# AS3364_DG412_bus_mixer_v1_2.net
KiCad netlist of a schematic drawn in EAGLE
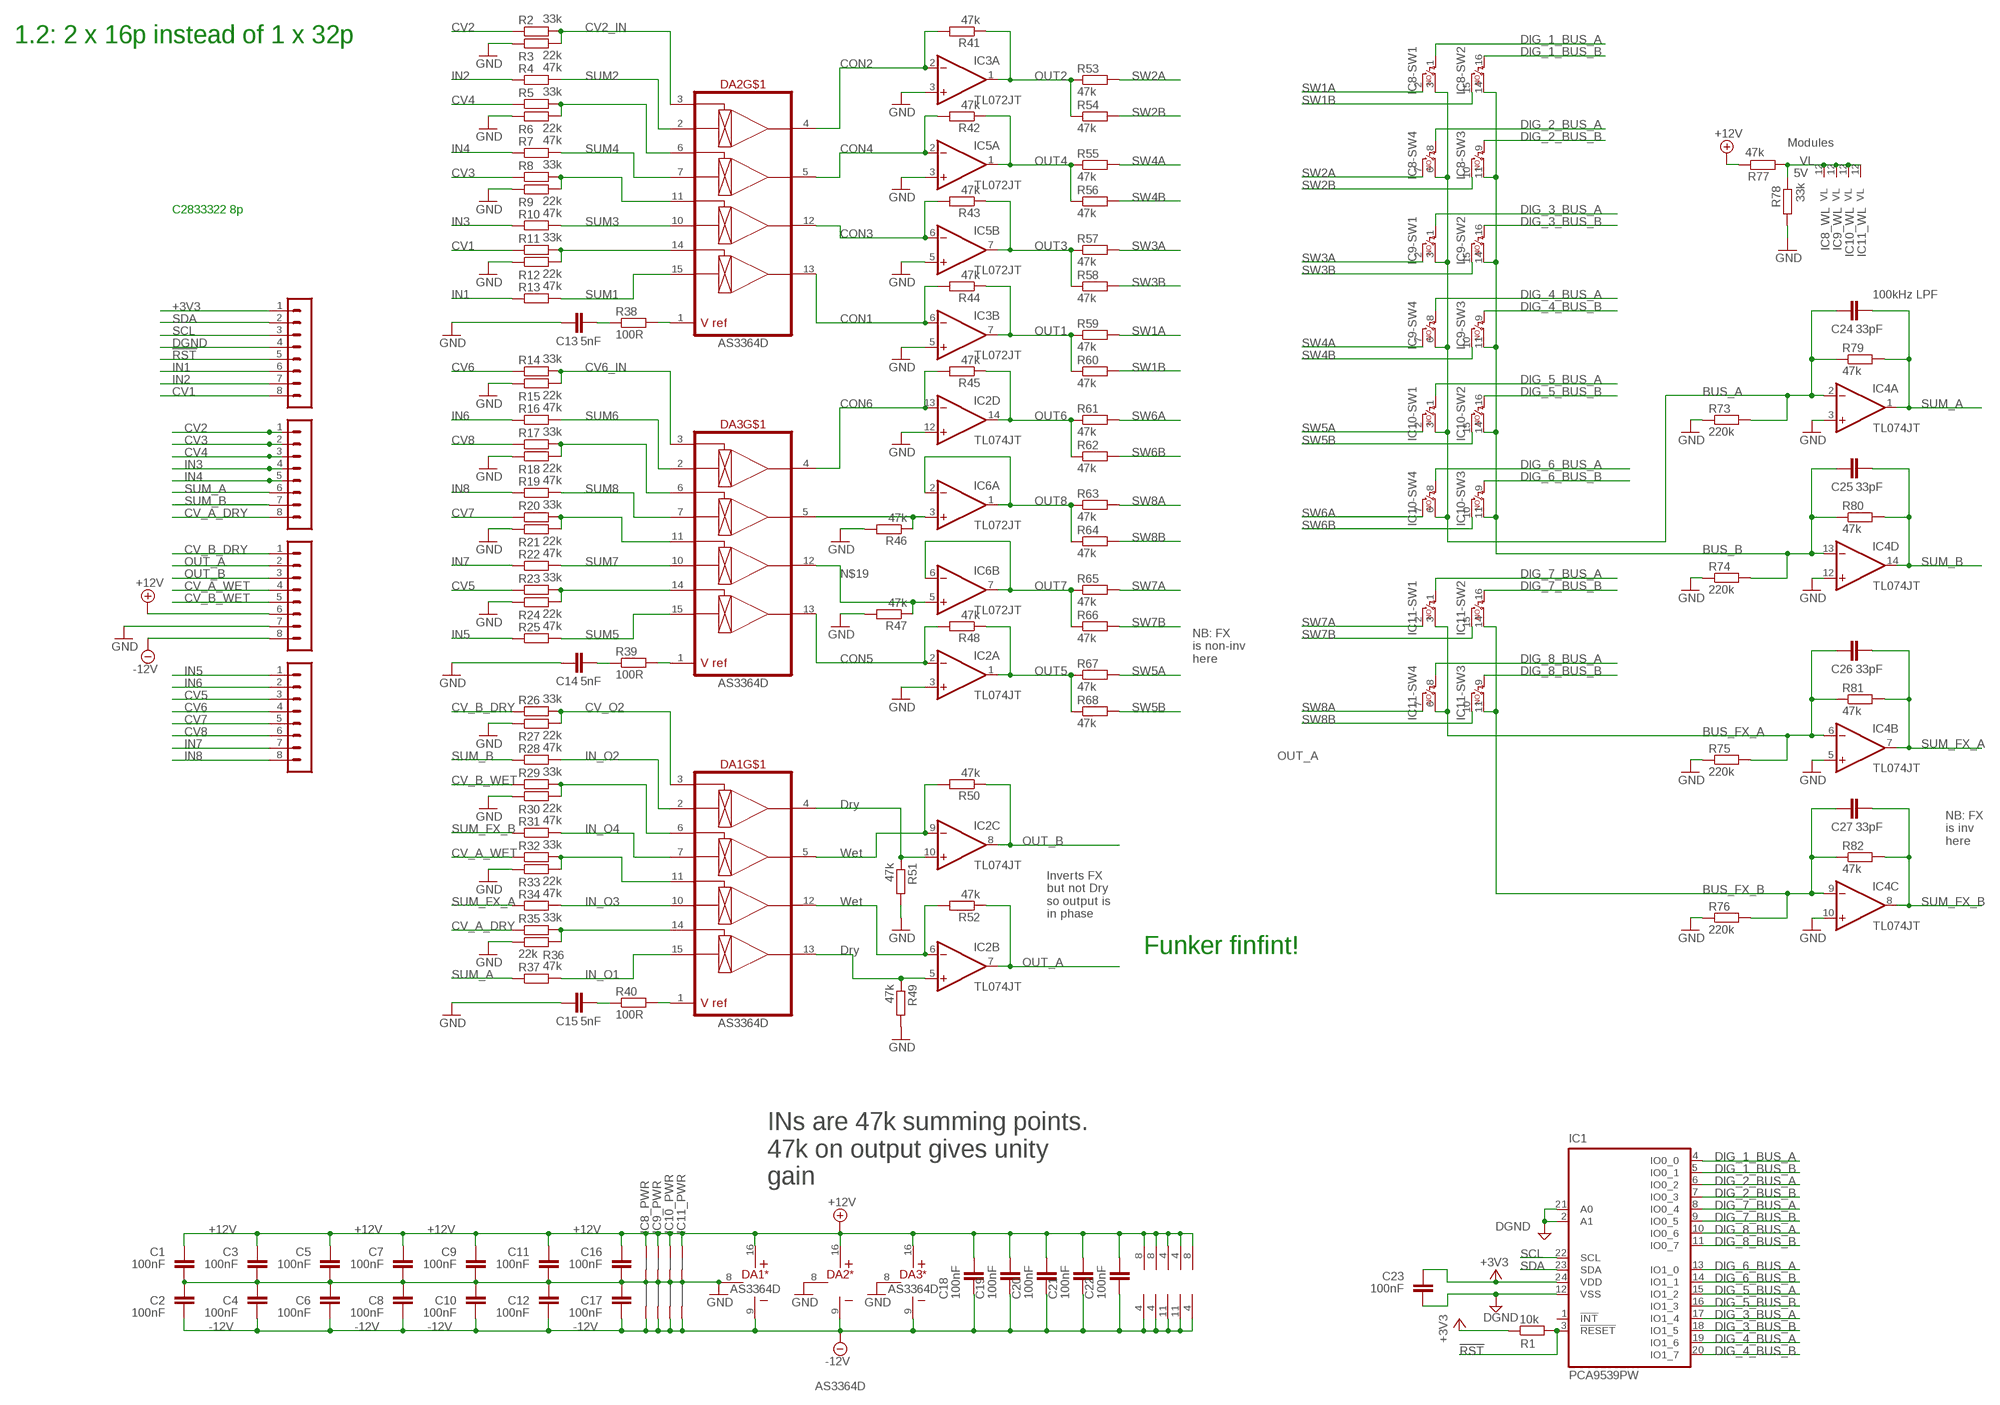
[diagram p0: schematic, sheet 1]

(export (version "E")
  (design (tool "Eeschema 10.0.6"))
  (components
    (comp (ref "C1")
      (value "100nF")
      (footprint "eagle-import:C0402")
      (libsource (lib "eagle-import") (part "C-EUC0402"))
    )
    (comp (ref "C2")
      (value "100nF")
      (footprint "eagle-import:C0402")
      (libsource (lib "eagle-import") (part "C-EUC0402"))
    )
    (comp (ref "C3")
      (value "100nF")
      (footprint "eagle-import:C0402")
      (libsource (lib "eagle-import") (part "C-EUC0402"))
    )
    (comp (ref "C4")
      (value "100nF")
      (footprint "eagle-import:C0402")
      (libsource (lib "eagle-import") (part "C-EUC0402"))
    )
    (comp (ref "C5")
      (value "100nF")
      (footprint "eagle-import:C0402")
      (libsource (lib "eagle-import") (part "C-EUC0402"))
    )
    (comp (ref "C6")
      (value "100nF")
      (footprint "eagle-import:C0402")
      (libsource (lib "eagle-import") (part "C-EUC0402"))
    )
    (comp (ref "C7")
      (value "100nF")
      (footprint "eagle-import:C0402")
      (libsource (lib "eagle-import") (part "C-EUC0402"))
    )
    (comp (ref "C8")
      (value "100nF")
      (footprint "eagle-import:C0402")
      (libsource (lib "eagle-import") (part "C-EUC0402"))
    )
    (comp (ref "C9")
      (value "100nF")
      (footprint "eagle-import:C0402")
      (libsource (lib "eagle-import") (part "C-EUC0402"))
    )
    (comp (ref "C10")
      (value "100nF")
      (footprint "eagle-import:C0402")
      (libsource (lib "eagle-import") (part "C-EUC0402"))
    )
    (comp (ref "C11")
      (value "100nF")
      (footprint "eagle-import:C0402")
      (libsource (lib "eagle-import") (part "C-EUC0402"))
    )
    (comp (ref "C12")
      (value "100nF")
      (footprint "eagle-import:C0402")
      (libsource (lib "eagle-import") (part "C-EUC0402"))
    )
    (comp (ref "C13")
      (value "5nF")
      (footprint "eagle-import:C0402-J")
      (libsource (lib "eagle-import") (part "C-EU-J"))
    )
    (comp (ref "C14")
      (value "5nF")
      (footprint "eagle-import:C0402-J")
      (libsource (lib "eagle-import") (part "C-EU-J"))
    )
    (comp (ref "C15")
      (value "5nF")
      (footprint "eagle-import:C0402-J")
      (libsource (lib "eagle-import") (part "C-EU-J"))
    )
    (comp (ref "C16")
      (value "100nF")
      (footprint "eagle-import:C0402")
      (libsource (lib "eagle-import") (part "C-EUC0402"))
    )
    (comp (ref "C17")
      (value "100nF")
      (footprint "eagle-import:C0402")
      (libsource (lib "eagle-import") (part "C-EUC0402"))
    )
    (comp (ref "C18")
      (value "100nF")
      (footprint "eagle-import:C0402")
      (libsource (lib "eagle-import") (part "C-EUC0402"))
    )
    (comp (ref "C19")
      (value "100nF")
      (footprint "eagle-import:C0402")
      (libsource (lib "eagle-import") (part "C-EUC0402"))
    )
    (comp (ref "C20")
      (value "100nF")
      (footprint "eagle-import:C0402")
      (libsource (lib "eagle-import") (part "C-EUC0402"))
    )
    (comp (ref "C21")
      (value "100nF")
      (footprint "eagle-import:C0402")
      (libsource (lib "eagle-import") (part "C-EUC0402"))
    )
    (comp (ref "C22")
      (value "100nF")
      (footprint "eagle-import:C0402")
      (libsource (lib "eagle-import") (part "C-EUC0402"))
    )
    (comp (ref "C23")
      (value "100nF")
      (footprint "eagle-import:C0402")
      (libsource (lib "eagle-import") (part "C-EUC0402"))
    )
    (comp (ref "C24")
      (value "33pF")
      (footprint "eagle-import:C0402-J")
      (libsource (lib "eagle-import") (part "C-EU-J"))
    )
    (comp (ref "C25")
      (value "33pF")
      (footprint "eagle-import:C0402-J")
      (libsource (lib "eagle-import") (part "C-EU-J"))
    )
    (comp (ref "C26")
      (value "33pF")
      (footprint "eagle-import:C0402-J")
      (libsource (lib "eagle-import") (part "C-EU-J"))
    )
    (comp (ref "C27")
      (value "33pF")
      (footprint "eagle-import:C0402-J")
      (libsource (lib "eagle-import") (part "C-EU-J"))
    )
    (comp (ref "DA1")
      (value "AS3364D")
      (footprint "eagle-import:DIL16J")
      (libsource (lib "eagle-import") (part "AS3364D"))
    )
    (comp (ref "DA2")
      (value "AS3364D")
      (footprint "eagle-import:DIL16J")
      (libsource (lib "eagle-import") (part "AS3364D"))
    )
    (comp (ref "DA3")
      (value "AS3364D")
      (footprint "eagle-import:DIL16J")
      (libsource (lib "eagle-import") (part "AS3364D"))
    )
    (comp (ref "IC1")
      (value "PCA9539PW")
      (footprint "eagle-import:TSSOP24J")
      (libsource (lib "eagle-import") (part "PCA9539PW"))
    )
    (comp (ref "IC2")
      (value "TL074JT")
      (footprint "eagle-import:TSSOP14J")
      (libsource (lib "eagle-import") (part "TL074JT"))
    )
    (comp (ref "IC3")
      (value "TL072JT")
      (footprint "eagle-import:TSSOP8J")
      (libsource (lib "eagle-import") (part "TL072JT"))
    )
    (comp (ref "IC4")
      (value "TL074JT")
      (footprint "eagle-import:TSSOP14J")
      (libsource (lib "eagle-import") (part "TL074JT"))
    )
    (comp (ref "IC5")
      (value "TL072JT")
      (footprint "eagle-import:TSSOP8J")
      (libsource (lib "eagle-import") (part "TL072JT"))
    )
    (comp (ref "IC6")
      (value "TL072JT")
      (footprint "eagle-import:TSSOP8J")
      (libsource (lib "eagle-import") (part "TL072JT"))
    )
    (comp (ref "IC8")
      (value "DG412-J")
      (footprint "eagle-import:DIL16J")
      (libsource (lib "eagle-import") (part "DG412-J"))
    )
    (comp (ref "IC9")
      (value "DG412-J")
      (footprint "eagle-import:DIL16J")
      (libsource (lib "eagle-import") (part "DG412-J"))
    )
    (comp (ref "IC10")
      (value "DG412-J")
      (footprint "eagle-import:DIL16J")
      (libsource (lib "eagle-import") (part "DG412-J"))
    )
    (comp (ref "IC11")
      (value "DG412-J")
      (footprint "eagle-import:DIL16J")
      (libsource (lib "eagle-import") (part "DG412-J"))
    )
    (comp (ref "R1")
      (value "10k")
      (footprint "eagle-import:R0402")
      (libsource (lib "eagle-import") (part "R-EU_R0402"))
    )
    (comp (ref "R2")
      (value "33k")
      (footprint "eagle-import:R0402")
      (libsource (lib "eagle-import") (part "R-EU_R0402"))
    )
    (comp (ref "R3")
      (value "22k")
      (footprint "eagle-import:R0402")
      (libsource (lib "eagle-import") (part "R-EU_R0402"))
    )
    (comp (ref "R4")
      (value "47k")
      (footprint "eagle-import:R0402")
      (libsource (lib "eagle-import") (part "R-EU_R0402"))
    )
    (comp (ref "R5")
      (value "33k")
      (footprint "eagle-import:R0402")
      (libsource (lib "eagle-import") (part "R-EU_R0402"))
    )
    (comp (ref "R6")
      (value "22k")
      (footprint "eagle-import:R0402")
      (libsource (lib "eagle-import") (part "R-EU_R0402"))
    )
    (comp (ref "R7")
      (value "47k")
      (footprint "eagle-import:R0402")
      (libsource (lib "eagle-import") (part "R-EU_R0402"))
    )
    (comp (ref "R8")
      (value "33k")
      (footprint "eagle-import:R0402")
      (libsource (lib "eagle-import") (part "R-EU_R0402"))
    )
    (comp (ref "R9")
      (value "22k")
      (footprint "eagle-import:R0402")
      (libsource (lib "eagle-import") (part "R-EU_R0402"))
    )
    (comp (ref "R10")
      (value "47k")
      (footprint "eagle-import:R0402")
      (libsource (lib "eagle-import") (part "R-EU_R0402"))
    )
    (comp (ref "R11")
      (value "33k")
      (footprint "eagle-import:R0402")
      (libsource (lib "eagle-import") (part "R-EU_R0402"))
    )
    (comp (ref "R12")
      (value "22k")
      (footprint "eagle-import:R0402")
      (libsource (lib "eagle-import") (part "R-EU_R0402"))
    )
    (comp (ref "R13")
      (value "47k")
      (footprint "eagle-import:R0402")
      (libsource (lib "eagle-import") (part "R-EU_R0402"))
    )
    (comp (ref "R14")
      (value "33k")
      (footprint "eagle-import:R0402")
      (libsource (lib "eagle-import") (part "R-EU_R0402"))
    )
    (comp (ref "R15")
      (value "22k")
      (footprint "eagle-import:R0402")
      (libsource (lib "eagle-import") (part "R-EU_R0402"))
    )
    (comp (ref "R16")
      (value "47k")
      (footprint "eagle-import:R0402")
      (libsource (lib "eagle-import") (part "R-EU_R0402"))
    )
    (comp (ref "R17")
      (value "33k")
      (footprint "eagle-import:R0402")
      (libsource (lib "eagle-import") (part "R-EU_R0402"))
    )
    (comp (ref "R18")
      (value "22k")
      (footprint "eagle-import:R0402")
      (libsource (lib "eagle-import") (part "R-EU_R0402"))
    )
    (comp (ref "R19")
      (value "47k")
      (footprint "eagle-import:R0402")
      (libsource (lib "eagle-import") (part "R-EU_R0402"))
    )
    (comp (ref "R20")
      (value "33k")
      (footprint "eagle-import:R0402")
      (libsource (lib "eagle-import") (part "R-EU_R0402"))
    )
    (comp (ref "R21")
      (value "22k")
      (footprint "eagle-import:R0402")
      (libsource (lib "eagle-import") (part "R-EU_R0402"))
    )
    (comp (ref "R22")
      (value "47k")
      (footprint "eagle-import:R0402")
      (libsource (lib "eagle-import") (part "R-EU_R0402"))
    )
    (comp (ref "R23")
      (value "33k")
      (footprint "eagle-import:R0402")
      (libsource (lib "eagle-import") (part "R-EU_R0402"))
    )
    (comp (ref "R24")
      (value "22k")
      (footprint "eagle-import:R0402")
      (libsource (lib "eagle-import") (part "R-EU_R0402"))
    )
    (comp (ref "R25")
      (value "47k")
      (footprint "eagle-import:R0402")
      (libsource (lib "eagle-import") (part "R-EU_R0402"))
    )
    (comp (ref "R26")
      (value "33k")
      (footprint "eagle-import:R0402")
      (libsource (lib "eagle-import") (part "R-EU_R0402"))
    )
    (comp (ref "R27")
      (value "22k")
      (footprint "eagle-import:R0402")
      (libsource (lib "eagle-import") (part "R-EU_R0402"))
    )
    (comp (ref "R28")
      (value "47k")
      (footprint "eagle-import:R0402")
      (libsource (lib "eagle-import") (part "R-EU_R0402"))
    )
    (comp (ref "R29")
      (value "33k")
      (footprint "eagle-import:R0402")
      (libsource (lib "eagle-import") (part "R-EU_R0402"))
    )
    (comp (ref "R30")
      (value "22k")
      (footprint "eagle-import:R0402")
      (libsource (lib "eagle-import") (part "R-EU_R0402"))
    )
    (comp (ref "R31")
      (value "47k")
      (footprint "eagle-import:R0402")
      (libsource (lib "eagle-import") (part "R-EU_R0402"))
    )
    (comp (ref "R32")
      (value "33k")
      (footprint "eagle-import:R0402")
      (libsource (lib "eagle-import") (part "R-EU_R0402"))
    )
    (comp (ref "R33")
      (value "22k")
      (footprint "eagle-import:R0402")
      (libsource (lib "eagle-import") (part "R-EU_R0402"))
    )
    (comp (ref "R34")
      (value "47k")
      (footprint "eagle-import:R0402")
      (libsource (lib "eagle-import") (part "R-EU_R0402"))
    )
    (comp (ref "R35")
      (value "33k")
      (footprint "eagle-import:R0402")
      (libsource (lib "eagle-import") (part "R-EU_R0402"))
    )
    (comp (ref "R36")
      (value "22k")
      (footprint "eagle-import:R0402")
      (libsource (lib "eagle-import") (part "R-EU_R0402"))
    )
    (comp (ref "R37")
      (value "47k")
      (footprint "eagle-import:R0402")
      (libsource (lib "eagle-import") (part "R-EU_R0402"))
    )
    (comp (ref "R38")
      (value "100R")
      (footprint "eagle-import:R0402")
      (libsource (lib "eagle-import") (part "R-EU_R0402"))
    )
    (comp (ref "R39")
      (value "100R")
      (footprint "eagle-import:R0402")
      (libsource (lib "eagle-import") (part "R-EU_R0402"))
    )
    (comp (ref "R40")
      (value "100R")
      (footprint "eagle-import:R0402")
      (libsource (lib "eagle-import") (part "R-EU_R0402"))
    )
    (comp (ref "R41")
      (value "47k")
      (footprint "eagle-import:R0402")
      (libsource (lib "eagle-import") (part "R-EU_R0402"))
    )
    (comp (ref "R42")
      (value "47k")
      (footprint "eagle-import:R0402")
      (libsource (lib "eagle-import") (part "R-EU_R0402"))
    )
    (comp (ref "R43")
      (value "47k")
      (footprint "eagle-import:R0402")
      (libsource (lib "eagle-import") (part "R-EU_R0402"))
    )
    (comp (ref "R44")
      (value "47k")
      (footprint "eagle-import:R0402")
      (libsource (lib "eagle-import") (part "R-EU_R0402"))
    )
    (comp (ref "R45")
      (value "47k")
      (footprint "eagle-import:R0402")
      (libsource (lib "eagle-import") (part "R-EU_R0402"))
    )
    (comp (ref "R46")
      (value "47k")
      (footprint "eagle-import:R0402")
      (libsource (lib "eagle-import") (part "R-EU_R0402"))
    )
    (comp (ref "R47")
      (value "47k")
      (footprint "eagle-import:R0402")
      (libsource (lib "eagle-import") (part "R-EU_R0402"))
    )
    (comp (ref "R48")
      (value "47k")
      (footprint "eagle-import:R0402")
      (libsource (lib "eagle-import") (part "R-EU_R0402"))
    )
    (comp (ref "R49")
      (value "47k")
      (footprint "eagle-import:R0402")
      (libsource (lib "eagle-import") (part "R-EU_R0402"))
    )
    (comp (ref "R50")
      (value "47k")
      (footprint "eagle-import:R0402")
      (libsource (lib "eagle-import") (part "R-EU_R0402"))
    )
    (comp (ref "R51")
      (value "47k")
      (footprint "eagle-import:R0402")
      (libsource (lib "eagle-import") (part "R-EU_R0402"))
    )
    (comp (ref "R52")
      (value "47k")
      (footprint "eagle-import:R0402")
      (libsource (lib "eagle-import") (part "R-EU_R0402"))
    )
    (comp (ref "R53")
      (value "47k")
      (footprint "eagle-import:R0402")
      (libsource (lib "eagle-import") (part "R-EU_R0402"))
    )
    (comp (ref "R54")
      (value "47k")
      (footprint "eagle-import:R0402")
      (libsource (lib "eagle-import") (part "R-EU_R0402"))
    )
    (comp (ref "R55")
      (value "47k")
      (footprint "eagle-import:R0402")
      (libsource (lib "eagle-import") (part "R-EU_R0402"))
    )
    (comp (ref "R56")
      (value "47k")
      (footprint "eagle-import:R0402")
      (libsource (lib "eagle-import") (part "R-EU_R0402"))
    )
    (comp (ref "R57")
      (value "47k")
      (footprint "eagle-import:R0402")
      (libsource (lib "eagle-import") (part "R-EU_R0402"))
    )
    (comp (ref "R58")
      (value "47k")
      (footprint "eagle-import:R0402")
      (libsource (lib "eagle-import") (part "R-EU_R0402"))
    )
    (comp (ref "R59")
      (value "47k")
      (footprint "eagle-import:R0402")
      (libsource (lib "eagle-import") (part "R-EU_R0402"))
    )
    (comp (ref "R60")
      (value "47k")
      (footprint "eagle-import:R0402")
      (libsource (lib "eagle-import") (part "R-EU_R0402"))
    )
    (comp (ref "R61")
      (value "47k")
      (footprint "eagle-import:R0402")
      (libsource (lib "eagle-import") (part "R-EU_R0402"))
    )
    (comp (ref "R62")
      (value "47k")
      (footprint "eagle-import:R0402")
      (libsource (lib "eagle-import") (part "R-EU_R0402"))
    )
    (comp (ref "R63")
      (value "47k")
      (footprint "eagle-import:R0402")
      (libsource (lib "eagle-import") (part "R-EU_R0402"))
    )
    (comp (ref "R64")
      (value "47k")
      (footprint "eagle-import:R0402")
      (libsource (lib "eagle-import") (part "R-EU_R0402"))
    )
    (comp (ref "R65")
      (value "47k")
      (footprint "eagle-import:R0402")
      (libsource (lib "eagle-import") (part "R-EU_R0402"))
    )
    (comp (ref "R66")
      (value "47k")
      (footprint "eagle-import:R0402")
      (libsource (lib "eagle-import") (part "R-EU_R0402"))
    )
    (comp (ref "R67")
      (value "47k")
      (footprint "eagle-import:R0402")
      (libsource (lib "eagle-import") (part "R-EU_R0402"))
    )
    (comp (ref "R68")
      (value "47k")
      (footprint "eagle-import:R0402")
      (libsource (lib "eagle-import") (part "R-EU_R0402"))
    )
    (comp (ref "R73")
      (value "220k")
      (footprint "eagle-import:R0402")
      (libsource (lib "eagle-import") (part "R-EU_R0402"))
    )
    (comp (ref "R74")
      (value "220k")
      (footprint "eagle-import:R0402")
      (libsource (lib "eagle-import") (part "R-EU_R0402"))
    )
    (comp (ref "R75")
      (value "220k")
      (footprint "eagle-import:R0402")
      (libsource (lib "eagle-import") (part "R-EU_R0402"))
    )
    (comp (ref "R76")
      (value "220k")
      (footprint "eagle-import:R0402")
      (libsource (lib "eagle-import") (part "R-EU_R0402"))
    )
    (comp (ref "R77")
      (value "47k")
      (footprint "eagle-import:R0402")
      (libsource (lib "eagle-import") (part "R-EU_R0402"))
    )
    (comp (ref "R78")
      (value "33k")
      (footprint "eagle-import:R0402")
      (libsource (lib "eagle-import") (part "R-EU_R0402"))
    )
    (comp (ref "R79")
      (value "47k")
      (footprint "eagle-import:R0402")
      (libsource (lib "eagle-import") (part "R-EU_R0402"))
    )
    (comp (ref "R80")
      (value "47k")
      (footprint "eagle-import:R0402")
      (libsource (lib "eagle-import") (part "R-EU_R0402"))
    )
    (comp (ref "R81")
      (value "47k")
      (footprint "eagle-import:R0402")
      (libsource (lib "eagle-import") (part "R-EU_R0402"))
    )
    (comp (ref "R82")
      (value "47k")
      (footprint "eagle-import:R0402")
      (libsource (lib "eagle-import") (part "R-EU_R0402"))
    )
    (comp (ref "SV1")
      (value "MA08-1JP")
      (footprint "eagle-import:SIP-PIN08-1J")
      (libsource (lib "eagle-import") (part "MA08-1JP"))
    )
    (comp (ref "SV3")
      (value "MA08-1JP")
      (footprint "eagle-import:SIP-PIN08-1J")
      (libsource (lib "eagle-import") (part "MA08-1JP"))
    )
    (comp (ref "SV4")
      (value "MA08-1JP")
      (footprint "eagle-import:SIP-PIN08-1J")
      (libsource (lib "eagle-import") (part "MA08-1JP"))
    )
    (comp (ref "SV33")
      (value "MA08-1JP")
      (footprint "eagle-import:SIP-PIN08-1J")
      (libsource (lib "eagle-import") (part "MA08-1JP"))
    )
  )
  (nets
    (net (code "1") (name "+3V3") (class "Default")
      (node (ref "C23") (pin "2") (pinfunction "2_2") (pintype "passive"))
      (node (ref "IC1") (pin "24") (pinfunction "VDD_24") (pintype "power_in"))
      (node (ref "R1") (pin "1") (pinfunction "1_1") (pintype "passive"))
      (node (ref "SV33") (pin "1") (pinfunction "1_1") (pintype "passive"))
    )
    (net (code "2") (name "+12V") (class "Default")
      (node (ref "C1") (pin "2") (pinfunction "2_2") (pintype "passive"))
      (node (ref "C11") (pin "2") (pinfunction "2_2") (pintype "passive"))
      (node (ref "C16") (pin "2") (pinfunction "2_2") (pintype "passive"))
      (node (ref "C18") (pin "2") (pinfunction "2_2") (pintype "passive"))
      (node (ref "C19") (pin "2") (pinfunction "2_2") (pintype "passive"))
      (node (ref "C20") (pin "2") (pinfunction "2_2") (pintype "passive"))
      (node (ref "C21") (pin "2") (pinfunction "2_2") (pintype "passive"))
      (node (ref "C22") (pin "2") (pinfunction "2_2") (pintype "passive"))
      (node (ref "C3") (pin "2") (pinfunction "2_2") (pintype "passive"))
      (node (ref "C5") (pin "2") (pinfunction "2_2") (pintype "passive"))
      (node (ref "C7") (pin "2") (pinfunction "2_2") (pintype "passive"))
      (node (ref "C9") (pin "2") (pinfunction "2_2") (pintype "passive"))
      (node (ref "DA1") (pin "16") (pinfunction "V+_16") (pintype "power_in"))
      (node (ref "DA2") (pin "16") (pinfunction "V+_16") (pintype "power_in"))
      (node (ref "DA3") (pin "16") (pinfunction "V+_16") (pintype "power_in"))
      (node (ref "IC10") (pin "13") (pinfunction "+15V_13") (pintype "power_in"))
      (node (ref "IC11") (pin "13") (pinfunction "+15V_13") (pintype "power_in"))
      (node (ref "IC2") (pin "4") (pinfunction "V+_4") (pintype "power_in"))
      (node (ref "IC3") (pin "8") (pinfunction "V+_8") (pintype "power_in"))
      (node (ref "IC4") (pin "4") (pinfunction "V+_4") (pintype "power_in"))
      (node (ref "IC5") (pin "8") (pinfunction "V+_8") (pintype "power_in"))
      (node (ref "IC6") (pin "8") (pinfunction "V+_8") (pintype "power_in"))
      (node (ref "IC8") (pin "13") (pinfunction "+15V_13") (pintype "power_in"))
      (node (ref "IC9") (pin "13") (pinfunction "+15V_13") (pintype "power_in"))
      (node (ref "R77") (pin "1") (pinfunction "1_1") (pintype "passive"))
      (node (ref "SV4") (pin "6") (pinfunction "6_6") (pintype "passive"))
    )
    (net (code "3") (name "-12V") (class "Default")
      (node (ref "C10") (pin "1") (pinfunction "1_1") (pintype "passive"))
      (node (ref "C12") (pin "1") (pinfunction "1_1") (pintype "passive"))
      (node (ref "C17") (pin "1") (pinfunction "1_1") (pintype "passive"))
      (node (ref "C18") (pin "1") (pinfunction "1_1") (pintype "passive"))
      (node (ref "C19") (pin "1") (pinfunction "1_1") (pintype "passive"))
      (node (ref "C2") (pin "1") (pinfunction "1_1") (pintype "passive"))
      (node (ref "C20") (pin "1") (pinfunction "1_1") (pintype "passive"))
      (node (ref "C21") (pin "1") (pinfunction "1_1") (pintype "passive"))
      (node (ref "C22") (pin "1") (pinfunction "1_1") (pintype "passive"))
      (node (ref "C4") (pin "1") (pinfunction "1_1") (pintype "passive"))
      (node (ref "C6") (pin "1") (pinfunction "1_1") (pintype "passive"))
      (node (ref "C8") (pin "1") (pinfunction "1_1") (pintype "passive"))
      (node (ref "DA1") (pin "9") (pinfunction "V-_9") (pintype "power_in"))
      (node (ref "DA2") (pin "9") (pinfunction "V-_9") (pintype "power_in"))
      (node (ref "DA3") (pin "9") (pinfunction "V-_9") (pintype "power_in"))
      (node (ref "IC10") (pin "4") (pinfunction "-15V_4") (pintype "power_in"))
      (node (ref "IC11") (pin "4") (pinfunction "-15V_4") (pintype "power_in"))
      (node (ref "IC2") (pin "11") (pinfunction "V-_11") (pintype "power_in"))
      (node (ref "IC3") (pin "4") (pinfunction "V-_4") (pintype "power_in"))
      (node (ref "IC4") (pin "11") (pinfunction "V-_11") (pintype "power_in"))
      (node (ref "IC5") (pin "4") (pinfunction "V-_4") (pintype "power_in"))
      (node (ref "IC6") (pin "4") (pinfunction "V-_4") (pintype "power_in"))
      (node (ref "IC8") (pin "4") (pinfunction "-15V_4") (pintype "power_in"))
      (node (ref "IC9") (pin "4") (pinfunction "-15V_4") (pintype "power_in"))
      (node (ref "SV4") (pin "8") (pinfunction "8_8") (pintype "passive"))
    )
    (net (code "4") (name "/BUS_A") (class "Default")
      (node (ref "C24") (pin "1") (pinfunction "1_1") (pintype "passive"))
      (node (ref "IC10") (pin "3") (pinfunction "S_3") (pintype "bidirectional"))
      (node (ref "IC10") (pin "6") (pinfunction "S_6") (pintype "bidirectional"))
      (node (ref "IC4") (pin "2") (pinfunction "-IN_2") (pintype "input"))
      (node (ref "IC8") (pin "3") (pinfunction "S_3") (pintype "bidirectional"))
      (node (ref "IC8") (pin "6") (pinfunction "S_6") (pintype "bidirectional"))
      (node (ref "IC9") (pin "3") (pinfunction "S_3") (pintype "bidirectional"))
      (node (ref "IC9") (pin "6") (pinfunction "S_6") (pintype "bidirectional"))
      (node (ref "R73") (pin "2") (pinfunction "2_2") (pintype "passive"))
      (node (ref "R79") (pin "1") (pinfunction "1_1") (pintype "passive"))
    )
    (net (code "5") (name "/BUS_B") (class "Default")
      (node (ref "C25") (pin "1") (pinfunction "1_1") (pintype "passive"))
      (node (ref "IC10") (pin "11") (pinfunction "S_11") (pintype "bidirectional"))
      (node (ref "IC10") (pin "14") (pinfunction "S_14") (pintype "bidirectional"))
      (node (ref "IC4") (pin "13") (pinfunction "-IN_13") (pintype "input"))
      (node (ref "IC8") (pin "11") (pinfunction "S_11") (pintype "bidirectional"))
      (node (ref "IC8") (pin "14") (pinfunction "S_14") (pintype "bidirectional"))
      (node (ref "IC9") (pin "11") (pinfunction "S_11") (pintype "bidirectional"))
      (node (ref "IC9") (pin "14") (pinfunction "S_14") (pintype "bidirectional"))
      (node (ref "R74") (pin "2") (pinfunction "2_2") (pintype "passive"))
      (node (ref "R80") (pin "1") (pinfunction "1_1") (pintype "passive"))
    )
    (net (code "6") (name "/BUS_FX_A") (class "Default")
      (node (ref "C26") (pin "1") (pinfunction "1_1") (pintype "passive"))
      (node (ref "IC11") (pin "3") (pinfunction "S_3") (pintype "bidirectional"))
      (node (ref "IC11") (pin "6") (pinfunction "S_6") (pintype "bidirectional"))
      (node (ref "IC4") (pin "6") (pinfunction "-IN_6") (pintype "input"))
      (node (ref "R75") (pin "2") (pinfunction "2_2") (pintype "passive"))
      (node (ref "R81") (pin "1") (pinfunction "1_1") (pintype "passive"))
    )
    (net (code "7") (name "/BUS_FX_B") (class "Default")
      (node (ref "C27") (pin "1") (pinfunction "1_1") (pintype "passive"))
      (node (ref "IC11") (pin "11") (pinfunction "S_11") (pintype "bidirectional"))
      (node (ref "IC11") (pin "14") (pinfunction "S_14") (pintype "bidirectional"))
      (node (ref "IC4") (pin "9") (pinfunction "-IN_9") (pintype "input"))
      (node (ref "R76") (pin "2") (pinfunction "2_2") (pintype "passive"))
      (node (ref "R82") (pin "1") (pinfunction "1_1") (pintype "passive"))
    )
    (net (code "8") (name "/CON1") (class "Default")
      (node (ref "DA2") (pin "13") (pinfunction "OUT4_13") (pintype "output"))
      (node (ref "IC3") (pin "6") (pinfunction "-IN_6") (pintype "input"))
      (node (ref "R44") (pin "2") (pinfunction "2_2") (pintype "passive"))
    )
    (net (code "9") (name "/CON2") (class "Default")
      (node (ref "DA2") (pin "4") (pinfunction "OUT1_4") (pintype "output"))
      (node (ref "IC3") (pin "2") (pinfunction "-IN_2") (pintype "input"))
      (node (ref "R41") (pin "2") (pinfunction "2_2") (pintype "passive"))
    )
    (net (code "10") (name "/CON3") (class "Default")
      (node (ref "DA2") (pin "12") (pinfunction "OUT3_12") (pintype "output"))
      (node (ref "IC5") (pin "6") (pinfunction "-IN_6") (pintype "input"))
      (node (ref "R43") (pin "2") (pinfunction "2_2") (pintype "passive"))
    )
    (net (code "11") (name "/CON4") (class "Default")
      (node (ref "DA2") (pin "5") (pinfunction "OUT2_5") (pintype "output"))
      (node (ref "IC5") (pin "2") (pinfunction "-IN_2") (pintype "input"))
      (node (ref "R42") (pin "2") (pinfunction "2_2") (pintype "passive"))
    )
    (net (code "12") (name "/CON5") (class "Default")
      (node (ref "DA3") (pin "13") (pinfunction "OUT4_13") (pintype "output"))
      (node (ref "IC2") (pin "2") (pinfunction "-IN_2") (pintype "input"))
      (node (ref "R48") (pin "2") (pinfunction "2_2") (pintype "passive"))
    )
    (net (code "13") (name "/CON6") (class "Default")
      (node (ref "DA3") (pin "4") (pinfunction "OUT1_4") (pintype "output"))
      (node (ref "IC2") (pin "13") (pinfunction "-IN_13") (pintype "input"))
      (node (ref "R45") (pin "2") (pinfunction "2_2") (pintype "passive"))
    )
    (net (code "14") (name "/CV1") (class "Default")
      (node (ref "R11") (pin "1") (pinfunction "1_1") (pintype "passive"))
      (node (ref "SV33") (pin "8") (pinfunction "8_8") (pintype "passive"))
    )
    (net (code "15") (name "/CV2") (class "Default")
      (node (ref "R2") (pin "1") (pinfunction "1_1") (pintype "passive"))
      (node (ref "SV1") (pin "1") (pinfunction "1_1") (pintype "passive"))
    )
    (net (code "16") (name "/CV2_IN") (class "Default")
      (node (ref "DA2") (pin "3") (pinfunction "CV1_3") (pintype "input"))
      (node (ref "R2") (pin "2") (pinfunction "2_2") (pintype "passive"))
      (node (ref "R3") (pin "2") (pinfunction "2_2") (pintype "passive"))
    )
    (net (code "17") (name "/CV3") (class "Default")
      (node (ref "R8") (pin "1") (pinfunction "1_1") (pintype "passive"))
      (node (ref "SV1") (pin "2") (pinfunction "2_2") (pintype "passive"))
    )
    (net (code "18") (name "/CV4") (class "Default")
      (node (ref "R5") (pin "1") (pinfunction "1_1") (pintype "passive"))
      (node (ref "SV1") (pin "3") (pinfunction "3_3") (pintype "passive"))
    )
    (net (code "19") (name "/CV5") (class "Default")
      (node (ref "R23") (pin "1") (pinfunction "1_1") (pintype "passive"))
      (node (ref "SV3") (pin "3") (pinfunction "3_3") (pintype "passive"))
    )
    (net (code "20") (name "/CV6") (class "Default")
      (node (ref "R14") (pin "1") (pinfunction "1_1") (pintype "passive"))
      (node (ref "SV3") (pin "4") (pinfunction "4_4") (pintype "passive"))
    )
    (net (code "21") (name "/CV6_IN") (class "Default")
      (node (ref "DA3") (pin "3") (pinfunction "CV1_3") (pintype "input"))
      (node (ref "R14") (pin "2") (pinfunction "2_2") (pintype "passive"))
      (node (ref "R15") (pin "2") (pinfunction "2_2") (pintype "passive"))
    )
    (net (code "22") (name "/CV7") (class "Default")
      (node (ref "R20") (pin "1") (pinfunction "1_1") (pintype "passive"))
      (node (ref "SV3") (pin "5") (pinfunction "5_5") (pintype "passive"))
    )
    (net (code "23") (name "/CV8") (class "Default")
      (node (ref "R17") (pin "1") (pinfunction "1_1") (pintype "passive"))
      (node (ref "SV3") (pin "6") (pinfunction "6_6") (pintype "passive"))
    )
    (net (code "24") (name "/CV_A_DRY") (class "Default")
      (node (ref "R35") (pin "1") (pinfunction "1_1") (pintype "passive"))
      (node (ref "SV1") (pin "8") (pinfunction "8_8") (pintype "passive"))
    )
    (net (code "25") (name "/CV_A_WET") (class "Default")
      (node (ref "R32") (pin "1") (pinfunction "1_1") (pintype "passive"))
      (node (ref "SV4") (pin "4") (pinfunction "4_4") (pintype "passive"))
    )
    (net (code "26") (name "/CV_B_DRY") (class "Default")
      (node (ref "R26") (pin "1") (pinfunction "1_1") (pintype "passive"))
      (node (ref "SV4") (pin "1") (pinfunction "1_1") (pintype "passive"))
    )
    (net (code "27") (name "/CV_B_WET") (class "Default")
      (node (ref "R29") (pin "1") (pinfunction "1_1") (pintype "passive"))
      (node (ref "SV4") (pin "5") (pinfunction "5_5") (pintype "passive"))
    )
    (net (code "28") (name "/CV_O2") (class "Default")
      (node (ref "DA1") (pin "3") (pinfunction "CV1_3") (pintype "input"))
      (node (ref "R26") (pin "2") (pinfunction "2_2") (pintype "passive"))
      (node (ref "R27") (pin "2") (pinfunction "2_2") (pintype "passive"))
    )
    (net (code "29") (name "/DIG_1_BUS_A") (class "Default")
      (node (ref "IC1") (pin "4") (pinfunction "IO0_0_4") (pintype "bidirectional"))
      (node (ref "IC8") (pin "1") (pinfunction "C_1") (pintype "bidirectional"))
    )
    (net (code "30") (name "/DIG_1_BUS_B") (class "Default")
      (node (ref "IC1") (pin "5") (pinfunction "IO0_1_5") (pintype "bidirectional"))
      (node (ref "IC8") (pin "16") (pinfunction "C_16") (pintype "bidirectional"))
    )
    (net (code "31") (name "/DIG_2_BUS_A") (class "Default")
      (node (ref "IC1") (pin "6") (pinfunction "IO0_2_6") (pintype "bidirectional"))
      (node (ref "IC8") (pin "8") (pinfunction "C_8") (pintype "bidirectional"))
    )
    (net (code "32") (name "/DIG_2_BUS_B") (class "Default")
      (node (ref "IC1") (pin "7") (pinfunction "IO0_3_7") (pintype "bidirectional"))
      (node (ref "IC8") (pin "9") (pinfunction "C_9") (pintype "bidirectional"))
    )
    (net (code "33") (name "/DIG_3_BUS_A") (class "Default")
      (node (ref "IC1") (pin "17") (pinfunction "IO1_4_17") (pintype "bidirectional"))
      (node (ref "IC9") (pin "1") (pinfunction "C_1") (pintype "bidirectional"))
    )
    (net (code "34") (name "/DIG_3_BUS_B") (class "Default")
      (node (ref "IC1") (pin "18") (pinfunction "IO1_5_18") (pintype "bidirectional"))
      (node (ref "IC9") (pin "16") (pinfunction "C_16") (pintype "bidirectional"))
    )
    (net (code "35") (name "/DIG_4_BUS_A") (class "Default")
      (node (ref "IC1") (pin "19") (pinfunction "IO1_6_19") (pintype "bidirectional"))
      (node (ref "IC9") (pin "8") (pinfunction "C_8") (pintype "bidirectional"))
    )
    (net (code "36") (name "/DIG_4_BUS_B") (class "Default")
      (node (ref "IC1") (pin "20") (pinfunction "IO1_7_20") (pintype "bidirectional"))
      (node (ref "IC9") (pin "9") (pinfunction "C_9") (pintype "bidirectional"))
    )
    (net (code "37") (name "/DIG_5_BUS_A") (class "Default")
      (node (ref "IC1") (pin "15") (pinfunction "IO1_2_15") (pintype "bidirectional"))
      (node (ref "IC10") (pin "1") (pinfunction "C_1") (pintype "bidirectional"))
    )
    (net (code "38") (name "/DIG_5_BUS_B") (class "Default")
      (node (ref "IC1") (pin "16") (pinfunction "IO1_3_16") (pintype "bidirectional"))
      (node (ref "IC10") (pin "16") (pinfunction "C_16") (pintype "bidirectional"))
    )
    (net (code "39") (name "/DIG_6_BUS_A") (class "Default")
      (node (ref "IC1") (pin "13") (pinfunction "IO1_0_13") (pintype "bidirectional"))
      (node (ref "IC10") (pin "8") (pinfunction "C_8") (pintype "bidirectional"))
    )
    (net (code "40") (name "/DIG_6_BUS_B") (class "Default")
      (node (ref "IC1") (pin "14") (pinfunction "IO1_1_14") (pintype "bidirectional"))
      (node (ref "IC10") (pin "9") (pinfunction "C_9") (pintype "bidirectional"))
    )
    (net (code "41") (name "/DIG_7_BUS_A") (class "Default")
      (node (ref "IC1") (pin "8") (pinfunction "IO0_4_8") (pintype "bidirectional"))
      (node (ref "IC11") (pin "1") (pinfunction "C_1") (pintype "bidirectional"))
    )
    (net (code "42") (name "/DIG_7_BUS_B") (class "Default")
      (node (ref "IC1") (pin "9") (pinfunction "IO0_5_9") (pintype "bidirectional"))
      (node (ref "IC11") (pin "16") (pinfunction "C_16") (pintype "bidirectional"))
    )
    (net (code "43") (name "/DIG_8_BUS_A") (class "Default")
      (node (ref "IC1") (pin "10") (pinfunction "IO0_6_10") (pintype "bidirectional"))
      (node (ref "IC11") (pin "8") (pinfunction "C_8") (pintype "bidirectional"))
    )
    (net (code "44") (name "/DIG_8_BUS_B") (class "Default")
      (node (ref "IC1") (pin "11") (pinfunction "IO0_7_11") (pintype "bidirectional"))
      (node (ref "IC11") (pin "9") (pinfunction "C_9") (pintype "bidirectional"))
    )
    (net (code "45") (name "/IN1") (class "Default")
      (node (ref "R13") (pin "1") (pinfunction "1_1") (pintype "passive"))
      (node (ref "SV33") (pin "6") (pinfunction "6_6") (pintype "passive"))
    )
    (net (code "46") (name "/IN2") (class "Default")
      (node (ref "R4") (pin "1") (pinfunction "1_1") (pintype "passive"))
      (node (ref "SV33") (pin "7") (pinfunction "7_7") (pintype "passive"))
    )
    (net (code "47") (name "/IN3") (class "Default")
      (node (ref "R10") (pin "1") (pinfunction "1_1") (pintype "passive"))
      (node (ref "SV1") (pin "4") (pinfunction "4_4") (pintype "passive"))
    )
    (net (code "48") (name "/IN4") (class "Default")
      (node (ref "R7") (pin "1") (pinfunction "1_1") (pintype "passive"))
      (node (ref "SV1") (pin "5") (pinfunction "5_5") (pintype "passive"))
    )
    (net (code "49") (name "/IN5") (class "Default")
      (node (ref "R25") (pin "1") (pinfunction "1_1") (pintype "passive"))
      (node (ref "SV3") (pin "1") (pinfunction "1_1") (pintype "passive"))
    )
    (net (code "50") (name "/IN6") (class "Default")
      (node (ref "R16") (pin "1") (pinfunction "1_1") (pintype "passive"))
      (node (ref "SV3") (pin "2") (pinfunction "2_2") (pintype "passive"))
    )
    (net (code "51") (name "/IN7") (class "Default")
      (node (ref "R22") (pin "1") (pinfunction "1_1") (pintype "passive"))
      (node (ref "SV3") (pin "7") (pinfunction "7_7") (pintype "passive"))
    )
    (net (code "52") (name "/IN8") (class "Default")
      (node (ref "R19") (pin "1") (pinfunction "1_1") (pintype "passive"))
      (node (ref "SV3") (pin "8") (pinfunction "8_8") (pintype "passive"))
    )
    (net (code "53") (name "/IN_O1") (class "Default")
      (node (ref "DA1") (pin "15") (pinfunction "IN4_15") (pintype "input"))
      (node (ref "R37") (pin "2") (pinfunction "2_2") (pintype "passive"))
    )
    (net (code "54") (name "/IN_O2") (class "Default")
      (node (ref "DA1") (pin "2") (pinfunction "IN1_2") (pintype "input"))
      (node (ref "R28") (pin "2") (pinfunction "2_2") (pintype "passive"))
    )
    (net (code "55") (name "/IN_O3") (class "Default")
      (node (ref "DA1") (pin "10") (pinfunction "IN3_10") (pintype "input"))
      (node (ref "R34") (pin "2") (pinfunction "2_2") (pintype "passive"))
    )
    (net (code "56") (name "/IN_O4") (class "Default")
      (node (ref "DA1") (pin "7") (pinfunction "IN2_7") (pintype "input"))
      (node (ref "R31") (pin "2") (pinfunction "2_2") (pintype "passive"))
    )
    (net (code "57") (name "/N$19") (class "Default")
      (node (ref "DA3") (pin "12") (pinfunction "OUT3_12") (pintype "output"))
      (node (ref "IC6") (pin "5") (pinfunction "+IN_5") (pintype "input"))
      (node (ref "R47") (pin "1") (pinfunction "1_1") (pintype "passive"))
    )
    (net (code "58") (name "/OUT1") (class "Default")
      (node (ref "IC3") (pin "7") (pinfunction "OUT_7") (pintype "output"))
      (node (ref "R44") (pin "1") (pinfunction "1_1") (pintype "passive"))
      (node (ref "R59") (pin "1") (pinfunction "1_1") (pintype "passive"))
      (node (ref "R60") (pin "1") (pinfunction "1_1") (pintype "passive"))
    )
    (net (code "59") (name "/OUT2") (class "Default")
      (node (ref "IC3") (pin "1") (pinfunction "OUT_1") (pintype "output"))
      (node (ref "R41") (pin "1") (pinfunction "1_1") (pintype "passive"))
      (node (ref "R53") (pin "1") (pinfunction "1_1") (pintype "passive"))
      (node (ref "R54") (pin "1") (pinfunction "1_1") (pintype "passive"))
    )
    (net (code "60") (name "/OUT3") (class "Default")
      (node (ref "IC5") (pin "7") (pinfunction "OUT_7") (pintype "output"))
      (node (ref "R43") (pin "1") (pinfunction "1_1") (pintype "passive"))
      (node (ref "R57") (pin "1") (pinfunction "1_1") (pintype "passive"))
      (node (ref "R58") (pin "1") (pinfunction "1_1") (pintype "passive"))
    )
    (net (code "61") (name "/OUT4") (class "Default")
      (node (ref "IC5") (pin "1") (pinfunction "OUT_1") (pintype "output"))
      (node (ref "R42") (pin "1") (pinfunction "1_1") (pintype "passive"))
      (node (ref "R55") (pin "1") (pinfunction "1_1") (pintype "passive"))
      (node (ref "R56") (pin "1") (pinfunction "1_1") (pintype "passive"))
    )
    (net (code "62") (name "/OUT5") (class "Default")
      (node (ref "IC2") (pin "1") (pinfunction "OUT_1") (pintype "output"))
      (node (ref "R48") (pin "1") (pinfunction "1_1") (pintype "passive"))
      (node (ref "R67") (pin "1") (pinfunction "1_1") (pintype "passive"))
      (node (ref "R68") (pin "1") (pinfunction "1_1") (pintype "passive"))
    )
    (net (code "63") (name "/OUT6") (class "Default")
      (node (ref "IC2") (pin "14") (pinfunction "OUT_14") (pintype "output"))
      (node (ref "R45") (pin "1") (pinfunction "1_1") (pintype "passive"))
      (node (ref "R61") (pin "1") (pinfunction "1_1") (pintype "passive"))
      (node (ref "R62") (pin "1") (pinfunction "1_1") (pintype "passive"))
    )
    (net (code "64") (name "/OUT7") (class "Default")
      (node (ref "IC6") (pin "6") (pinfunction "-IN_6") (pintype "input"))
      (node (ref "IC6") (pin "7") (pinfunction "OUT_7") (pintype "output"))
      (node (ref "R65") (pin "1") (pinfunction "1_1") (pintype "passive"))
      (node (ref "R66") (pin "1") (pinfunction "1_1") (pintype "passive"))
    )
    (net (code "65") (name "/OUT8") (class "Default")
      (node (ref "IC6") (pin "1") (pinfunction "OUT_1") (pintype "output"))
      (node (ref "IC6") (pin "2") (pinfunction "-IN_2") (pintype "input"))
      (node (ref "R63") (pin "1") (pinfunction "1_1") (pintype "passive"))
      (node (ref "R64") (pin "1") (pinfunction "1_1") (pintype "passive"))
    )
    (net (code "66") (name "/OUT_A") (class "Default")
      (node (ref "IC2") (pin "7") (pinfunction "OUT_7") (pintype "output"))
      (node (ref "R52") (pin "1") (pinfunction "1_1") (pintype "passive"))
      (node (ref "SV4") (pin "2") (pinfunction "2_2") (pintype "passive"))
    )
    (net (code "67") (name "/OUT_B") (class "Default")
      (node (ref "IC2") (pin "8") (pinfunction "OUT_8") (pintype "output"))
      (node (ref "R50") (pin "1") (pinfunction "1_1") (pintype "passive"))
      (node (ref "SV4") (pin "3") (pinfunction "3_3") (pintype "passive"))
    )
    (net (code "68") (name "/SCL") (class "Default")
      (node (ref "IC1") (pin "22") (pinfunction "SCL_22") (pintype "bidirectional"))
      (node (ref "SV33") (pin "3") (pinfunction "3_3") (pintype "passive"))
    )
    (net (code "69") (name "/SDA") (class "Default")
      (node (ref "IC1") (pin "23") (pinfunction "SDA_23") (pintype "bidirectional"))
      (node (ref "SV33") (pin "2") (pinfunction "2_2") (pintype "passive"))
    )
    (net (code "70") (name "/SUM1") (class "Default")
      (node (ref "DA2") (pin "15") (pinfunction "IN4_15") (pintype "input"))
      (node (ref "R13") (pin "2") (pinfunction "2_2") (pintype "passive"))
    )
    (net (code "71") (name "/SUM2") (class "Default")
      (node (ref "DA2") (pin "2") (pinfunction "IN1_2") (pintype "input"))
      (node (ref "R4") (pin "2") (pinfunction "2_2") (pintype "passive"))
    )
    (net (code "72") (name "/SUM3") (class "Default")
      (node (ref "DA2") (pin "10") (pinfunction "IN3_10") (pintype "input"))
      (node (ref "R10") (pin "2") (pinfunction "2_2") (pintype "passive"))
    )
    (net (code "73") (name "/SUM4") (class "Default")
      (node (ref "DA2") (pin "7") (pinfunction "IN2_7") (pintype "input"))
      (node (ref "R7") (pin "2") (pinfunction "2_2") (pintype "passive"))
    )
    (net (code "74") (name "/SUM5") (class "Default")
      (node (ref "DA3") (pin "15") (pinfunction "IN4_15") (pintype "input"))
      (node (ref "R25") (pin "2") (pinfunction "2_2") (pintype "passive"))
    )
    (net (code "75") (name "/SUM6") (class "Default")
      (node (ref "DA3") (pin "2") (pinfunction "IN1_2") (pintype "input"))
      (node (ref "R16") (pin "2") (pinfunction "2_2") (pintype "passive"))
    )
    (net (code "76") (name "/SUM7") (class "Default")
      (node (ref "DA3") (pin "10") (pinfunction "IN3_10") (pintype "input"))
      (node (ref "R22") (pin "2") (pinfunction "2_2") (pintype "passive"))
    )
    (net (code "77") (name "/SUM8") (class "Default")
      (node (ref "DA3") (pin "7") (pinfunction "IN2_7") (pintype "input"))
      (node (ref "R19") (pin "2") (pinfunction "2_2") (pintype "passive"))
    )
    (net (code "78") (name "/SUM_A") (class "Default")
      (node (ref "C24") (pin "2") (pinfunction "2_2") (pintype "passive"))
      (node (ref "IC4") (pin "1") (pinfunction "OUT_1") (pintype "output"))
      (node (ref "R37") (pin "1") (pinfunction "1_1") (pintype "passive"))
      (node (ref "R79") (pin "2") (pinfunction "2_2") (pintype "passive"))
      (node (ref "SV1") (pin "6") (pinfunction "6_6") (pintype "passive"))
    )
    (net (code "79") (name "/SUM_B") (class "Default")
      (node (ref "C25") (pin "2") (pinfunction "2_2") (pintype "passive"))
      (node (ref "IC4") (pin "14") (pinfunction "OUT_14") (pintype "output"))
      (node (ref "R28") (pin "1") (pinfunction "1_1") (pintype "passive"))
      (node (ref "R80") (pin "2") (pinfunction "2_2") (pintype "passive"))
      (node (ref "SV1") (pin "7") (pinfunction "7_7") (pintype "passive"))
    )
    (net (code "80") (name "/SUM_FX_A") (class "Default")
      (node (ref "C26") (pin "2") (pinfunction "2_2") (pintype "passive"))
      (node (ref "IC4") (pin "7") (pinfunction "OUT_7") (pintype "output"))
      (node (ref "R34") (pin "1") (pinfunction "1_1") (pintype "passive"))
      (node (ref "R81") (pin "2") (pinfunction "2_2") (pintype "passive"))
    )
    (net (code "81") (name "/SUM_FX_B") (class "Default")
      (node (ref "C27") (pin "2") (pinfunction "2_2") (pintype "passive"))
      (node (ref "IC4") (pin "8") (pinfunction "OUT_8") (pintype "output"))
      (node (ref "R31") (pin "1") (pinfunction "1_1") (pintype "passive"))
      (node (ref "R82") (pin "2") (pinfunction "2_2") (pintype "passive"))
    )
    (net (code "82") (name "/SW1A") (class "Default")
      (node (ref "IC8") (pin "2") (pinfunction "D_2") (pintype "bidirectional"))
      (node (ref "R59") (pin "2") (pinfunction "2_2") (pintype "passive"))
    )
    (net (code "83") (name "/SW1B") (class "Default")
      (node (ref "IC8") (pin "15") (pinfunction "D_15") (pintype "bidirectional"))
      (node (ref "R60") (pin "2") (pinfunction "2_2") (pintype "passive"))
    )
    (net (code "84") (name "/SW2A") (class "Default")
      (node (ref "IC8") (pin "7") (pinfunction "D_7") (pintype "bidirectional"))
      (node (ref "R53") (pin "2") (pinfunction "2_2") (pintype "passive"))
    )
    (net (code "85") (name "/SW2B") (class "Default")
      (node (ref "IC8") (pin "10") (pinfunction "D_10") (pintype "bidirectional"))
      (node (ref "R54") (pin "2") (pinfunction "2_2") (pintype "passive"))
    )
    (net (code "86") (name "/SW3A") (class "Default")
      (node (ref "IC9") (pin "2") (pinfunction "D_2") (pintype "bidirectional"))
      (node (ref "R57") (pin "2") (pinfunction "2_2") (pintype "passive"))
    )
    (net (code "87") (name "/SW3B") (class "Default")
      (node (ref "IC9") (pin "15") (pinfunction "D_15") (pintype "bidirectional"))
      (node (ref "R58") (pin "2") (pinfunction "2_2") (pintype "passive"))
    )
    (net (code "88") (name "/SW4A") (class "Default")
      (node (ref "IC9") (pin "7") (pinfunction "D_7") (pintype "bidirectional"))
      (node (ref "R55") (pin "2") (pinfunction "2_2") (pintype "passive"))
    )
    (net (code "89") (name "/SW4B") (class "Default")
      (node (ref "IC9") (pin "10") (pinfunction "D_10") (pintype "bidirectional"))
      (node (ref "R56") (pin "2") (pinfunction "2_2") (pintype "passive"))
    )
    (net (code "90") (name "/SW5A") (class "Default")
      (node (ref "IC10") (pin "2") (pinfunction "D_2") (pintype "bidirectional"))
      (node (ref "R67") (pin "2") (pinfunction "2_2") (pintype "passive"))
    )
    (net (code "91") (name "/SW5B") (class "Default")
      (node (ref "IC10") (pin "15") (pinfunction "D_15") (pintype "bidirectional"))
      (node (ref "R68") (pin "2") (pinfunction "2_2") (pintype "passive"))
    )
    (net (code "92") (name "/SW6A") (class "Default")
      (node (ref "IC10") (pin "7") (pinfunction "D_7") (pintype "bidirectional"))
      (node (ref "R61") (pin "2") (pinfunction "2_2") (pintype "passive"))
    )
    (net (code "93") (name "/SW6B") (class "Default")
      (node (ref "IC10") (pin "10") (pinfunction "D_10") (pintype "bidirectional"))
      (node (ref "R62") (pin "2") (pinfunction "2_2") (pintype "passive"))
    )
    (net (code "94") (name "/SW7A") (class "Default")
      (node (ref "IC11") (pin "2") (pinfunction "D_2") (pintype "bidirectional"))
      (node (ref "R65") (pin "2") (pinfunction "2_2") (pintype "passive"))
    )
    (net (code "95") (name "/SW7B") (class "Default")
      (node (ref "IC11") (pin "15") (pinfunction "D_15") (pintype "bidirectional"))
      (node (ref "R66") (pin "2") (pinfunction "2_2") (pintype "passive"))
    )
    (net (code "96") (name "/SW8A") (class "Default")
      (node (ref "IC11") (pin "7") (pinfunction "D_7") (pintype "bidirectional"))
      (node (ref "R63") (pin "2") (pinfunction "2_2") (pintype "passive"))
    )
    (net (code "97") (name "/SW8B") (class "Default")
      (node (ref "IC11") (pin "10") (pinfunction "D_10") (pintype "bidirectional"))
      (node (ref "R64") (pin "2") (pinfunction "2_2") (pintype "passive"))
    )
    (net (code "98") (name "/VL") (class "Default")
      (node (ref "IC10") (pin "12") (pinfunction "VL_12") (pintype "bidirectional"))
      (node (ref "IC11") (pin "12") (pinfunction "VL_12") (pintype "bidirectional"))
      (node (ref "IC8") (pin "12") (pinfunction "VL_12") (pintype "bidirectional"))
      (node (ref "IC9") (pin "12") (pinfunction "VL_12") (pintype "bidirectional"))
      (node (ref "R77") (pin "2") (pinfunction "2_2") (pintype "passive"))
      (node (ref "R78") (pin "1") (pinfunction "1_1") (pintype "passive"))
    )
    (net (code "99") (name "/~{RST}") (class "Default")
      (node (ref "IC1") (pin "3") (pinfunction "~{RESET}_3") (pintype "bidirectional"))
      (node (ref "R1") (pin "2") (pinfunction "2_2") (pintype "passive"))
      (node (ref "SV33") (pin "5") (pinfunction "5_5") (pintype "passive"))
    )
    (net (code "100") (name "DGND") (class "Default")
      (node (ref "C23") (pin "1") (pinfunction "1_1") (pintype "passive"))
      (node (ref "IC1") (pin "12") (pinfunction "VSS_12") (pintype "power_in"))
      (node (ref "IC1") (pin "2") (pinfunction "A1_2") (pintype "bidirectional"))
      (node (ref "IC1") (pin "21") (pinfunction "A0_21") (pintype "bidirectional"))
      (node (ref "SV33") (pin "4") (pinfunction "4_4") (pintype "passive"))
    )
    (net (code "101") (name "GND") (class "Default")
      (node (ref "C1") (pin "1") (pinfunction "1_1") (pintype "passive"))
      (node (ref "C10") (pin "2") (pinfunction "2_2") (pintype "passive"))
      (node (ref "C11") (pin "1") (pinfunction "1_1") (pintype "passive"))
      (node (ref "C12") (pin "2") (pinfunction "2_2") (pintype "passive"))
      (node (ref "C13") (pin "1") (pinfunction "1_1") (pintype "passive"))
      (node (ref "C14") (pin "1") (pinfunction "1_1") (pintype "passive"))
      (node (ref "C15") (pin "1") (pinfunction "1_1") (pintype "passive"))
      (node (ref "C16") (pin "1") (pinfunction "1_1") (pintype "passive"))
      (node (ref "C17") (pin "2") (pinfunction "2_2") (pintype "passive"))
      (node (ref "C2") (pin "2") (pinfunction "2_2") (pintype "passive"))
      (node (ref "C3") (pin "1") (pinfunction "1_1") (pintype "passive"))
      (node (ref "C4") (pin "2") (pinfunction "2_2") (pintype "passive"))
      (node (ref "C5") (pin "1") (pinfunction "1_1") (pintype "passive"))
      (node (ref "C6") (pin "2") (pinfunction "2_2") (pintype "passive"))
      (node (ref "C7") (pin "1") (pinfunction "1_1") (pintype "passive"))
      (node (ref "C8") (pin "2") (pinfunction "2_2") (pintype "passive"))
      (node (ref "C9") (pin "1") (pinfunction "1_1") (pintype "passive"))
      (node (ref "DA1") (pin "8") (pinfunction "GND_8") (pintype "power_in"))
      (node (ref "DA2") (pin "8") (pinfunction "GND_8") (pintype "power_in"))
      (node (ref "DA3") (pin "8") (pinfunction "GND_8") (pintype "power_in"))
      (node (ref "IC10") (pin "5") (pinfunction "AGND_5") (pintype "power_in"))
      (node (ref "IC11") (pin "5") (pinfunction "AGND_5") (pintype "power_in"))
      (node (ref "IC2") (pin "12") (pinfunction "+IN_12") (pintype "input"))
      (node (ref "IC2") (pin "3") (pinfunction "+IN_3") (pintype "input"))
      (node (ref "IC3") (pin "3") (pinfunction "+IN_3") (pintype "input"))
      (node (ref "IC3") (pin "5") (pinfunction "+IN_5") (pintype "input"))
      (node (ref "IC4") (pin "10") (pinfunction "+IN_10") (pintype "input"))
      (node (ref "IC4") (pin "12") (pinfunction "+IN_12") (pintype "input"))
      (node (ref "IC4") (pin "3") (pinfunction "+IN_3") (pintype "input"))
      (node (ref "IC4") (pin "5") (pinfunction "+IN_5") (pintype "input"))
      (node (ref "IC5") (pin "3") (pinfunction "+IN_3") (pintype "input"))
      (node (ref "IC5") (pin "5") (pinfunction "+IN_5") (pintype "input"))
      (node (ref "IC8") (pin "5") (pinfunction "AGND_5") (pintype "power_in"))
      (node (ref "IC9") (pin "5") (pinfunction "AGND_5") (pintype "power_in"))
      (node (ref "R12") (pin "1") (pinfunction "1_1") (pintype "passive"))
      (node (ref "R15") (pin "1") (pinfunction "1_1") (pintype "passive"))
      (node (ref "R18") (pin "1") (pinfunction "1_1") (pintype "passive"))
      (node (ref "R21") (pin "1") (pinfunction "1_1") (pintype "passive"))
      (node (ref "R24") (pin "1") (pinfunction "1_1") (pintype "passive"))
      (node (ref "R27") (pin "1") (pinfunction "1_1") (pintype "passive"))
      (node (ref "R3") (pin "1") (pinfunction "1_1") (pintype "passive"))
      (node (ref "R30") (pin "1") (pinfunction "1_1") (pintype "passive"))
      (node (ref "R33") (pin "1") (pinfunction "1_1") (pintype "passive"))
      (node (ref "R36") (pin "1") (pinfunction "1_1") (pintype "passive"))
      (node (ref "R46") (pin "2") (pinfunction "2_2") (pintype "passive"))
      (node (ref "R47") (pin "2") (pinfunction "2_2") (pintype "passive"))
      (node (ref "R49") (pin "2") (pinfunction "2_2") (pintype "passive"))
      (node (ref "R51") (pin "2") (pinfunction "2_2") (pintype "passive"))
      (node (ref "R6") (pin "1") (pinfunction "1_1") (pintype "passive"))
      (node (ref "R73") (pin "1") (pinfunction "1_1") (pintype "passive"))
      (node (ref "R74") (pin "1") (pinfunction "1_1") (pintype "passive"))
      (node (ref "R75") (pin "1") (pinfunction "1_1") (pintype "passive"))
      (node (ref "R76") (pin "1") (pinfunction "1_1") (pintype "passive"))
      (node (ref "R78") (pin "2") (pinfunction "2_2") (pintype "passive"))
      (node (ref "R9") (pin "1") (pinfunction "1_1") (pintype "passive"))
      (node (ref "SV4") (pin "7") (pinfunction "7_7") (pintype "passive"))
    )
    (net (code "102") (name "Net-(C13-Pad2)") (class "Default")
      (node (ref "C13") (pin "2") (pinfunction "2_2") (pintype "passive"))
      (node (ref "R38") (pin "1") (pinfunction "1_1") (pintype "passive"))
    )
    (net (code "103") (name "Net-(C14-Pad2)") (class "Default")
      (node (ref "C14") (pin "2") (pinfunction "2_2") (pintype "passive"))
      (node (ref "R39") (pin "1") (pinfunction "1_1") (pintype "passive"))
    )
    (net (code "104") (name "Net-(C15-Pad2)") (class "Default")
      (node (ref "C15") (pin "2") (pinfunction "2_2") (pintype "passive"))
      (node (ref "R40") (pin "1") (pinfunction "1_1") (pintype "passive"))
    )
    (net (code "105") (name "Net-(DA1B-CV2)") (class "Default")
      (node (ref "DA1") (pin "6") (pinfunction "CV2_6") (pintype "input"))
      (node (ref "R29") (pin "2") (pinfunction "2_2") (pintype "passive"))
      (node (ref "R30") (pin "2") (pinfunction "2_2") (pintype "passive"))
    )
    (net (code "106") (name "Net-(DA1B-CV3)") (class "Default")
      (node (ref "DA1") (pin "11") (pinfunction "CV3_11") (pintype "input"))
      (node (ref "R32") (pin "2") (pinfunction "2_2") (pintype "passive"))
      (node (ref "R33") (pin "2") (pinfunction "2_2") (pintype "passive"))
    )
    (net (code "107") (name "Net-(DA1B-CV4)") (class "Default")
      (node (ref "DA1") (pin "14") (pinfunction "CV4_14") (pintype "input"))
      (node (ref "R35") (pin "2") (pinfunction "2_2") (pintype "passive"))
      (node (ref "R36") (pin "2") (pinfunction "2_2") (pintype "passive"))
    )
    (net (code "108") (name "Net-(DA1B-OUT1)") (class "Default")
      (node (ref "DA1") (pin "4") (pinfunction "OUT1_4") (pintype "output"))
      (node (ref "IC2") (pin "10") (pinfunction "+IN_10") (pintype "input"))
      (node (ref "R51") (pin "1") (pinfunction "1_1") (pintype "passive"))
    )
    (net (code "109") (name "Net-(DA1B-OUT2)") (class "Default")
      (node (ref "DA1") (pin "5") (pinfunction "OUT2_5") (pintype "output"))
      (node (ref "IC2") (pin "9") (pinfunction "-IN_9") (pintype "input"))
      (node (ref "R50") (pin "2") (pinfunction "2_2") (pintype "passive"))
    )
    (net (code "110") (name "Net-(DA1B-OUT3)") (class "Default")
      (node (ref "DA1") (pin "12") (pinfunction "OUT3_12") (pintype "output"))
      (node (ref "IC2") (pin "6") (pinfunction "-IN_6") (pintype "input"))
      (node (ref "R52") (pin "2") (pinfunction "2_2") (pintype "passive"))
    )
    (net (code "111") (name "Net-(DA1B-OUT4)") (class "Default")
      (node (ref "DA1") (pin "13") (pinfunction "OUT4_13") (pintype "output"))
      (node (ref "IC2") (pin "5") (pinfunction "+IN_5") (pintype "input"))
      (node (ref "R49") (pin "1") (pinfunction "1_1") (pintype "passive"))
    )
    (net (code "112") (name "Net-(DA1B-VREF)") (class "Default")
      (node (ref "DA1") (pin "1") (pinfunction "VREF_1") (pintype "output"))
      (node (ref "R40") (pin "2") (pinfunction "2_2") (pintype "passive"))
    )
    (net (code "113") (name "Net-(DA2B-CV2)") (class "Default")
      (node (ref "DA2") (pin "6") (pinfunction "CV2_6") (pintype "input"))
      (node (ref "R5") (pin "2") (pinfunction "2_2") (pintype "passive"))
      (node (ref "R6") (pin "2") (pinfunction "2_2") (pintype "passive"))
    )
    (net (code "114") (name "Net-(DA2B-CV3)") (class "Default")
      (node (ref "DA2") (pin "11") (pinfunction "CV3_11") (pintype "input"))
      (node (ref "R8") (pin "2") (pinfunction "2_2") (pintype "passive"))
      (node (ref "R9") (pin "2") (pinfunction "2_2") (pintype "passive"))
    )
    (net (code "115") (name "Net-(DA2B-CV4)") (class "Default")
      (node (ref "DA2") (pin "14") (pinfunction "CV4_14") (pintype "input"))
      (node (ref "R11") (pin "2") (pinfunction "2_2") (pintype "passive"))
      (node (ref "R12") (pin "2") (pinfunction "2_2") (pintype "passive"))
    )
    (net (code "116") (name "Net-(DA2B-VREF)") (class "Default")
      (node (ref "DA2") (pin "1") (pinfunction "VREF_1") (pintype "output"))
      (node (ref "R38") (pin "2") (pinfunction "2_2") (pintype "passive"))
    )
    (net (code "117") (name "Net-(DA3B-CV2)") (class "Default")
      (node (ref "DA3") (pin "6") (pinfunction "CV2_6") (pintype "input"))
      (node (ref "R17") (pin "2") (pinfunction "2_2") (pintype "passive"))
      (node (ref "R18") (pin "2") (pinfunction "2_2") (pintype "passive"))
    )
    (net (code "118") (name "Net-(DA3B-CV3)") (class "Default")
      (node (ref "DA3") (pin "11") (pinfunction "CV3_11") (pintype "input"))
      (node (ref "R20") (pin "2") (pinfunction "2_2") (pintype "passive"))
      (node (ref "R21") (pin "2") (pinfunction "2_2") (pintype "passive"))
    )
    (net (code "119") (name "Net-(DA3B-CV4)") (class "Default")
      (node (ref "DA3") (pin "14") (pinfunction "CV4_14") (pintype "input"))
      (node (ref "R23") (pin "2") (pinfunction "2_2") (pintype "passive"))
      (node (ref "R24") (pin "2") (pinfunction "2_2") (pintype "passive"))
    )
    (net (code "120") (name "Net-(DA3B-OUT2)") (class "Default")
      (node (ref "DA3") (pin "5") (pinfunction "OUT2_5") (pintype "output"))
      (node (ref "IC6") (pin "3") (pinfunction "+IN_3") (pintype "input"))
      (node (ref "R46") (pin "1") (pinfunction "1_1") (pintype "passive"))
    )
    (net (code "121") (name "Net-(DA3B-VREF)") (class "Default")
      (node (ref "DA3") (pin "1") (pinfunction "VREF_1") (pintype "output"))
      (node (ref "R39") (pin "2") (pinfunction "2_2") (pintype "passive"))
    )
    (net (code "122") (name "unconnected-(IC1-~{INT}-Pad1)") (class "Default")
      (node (ref "IC1") (pin "1") (pinfunction "~{INT}_1") (pintype "bidirectional"))
    )
  )
)
